# encoderBreakout1.net
KiCad netlist of a schematic drawn in Altium Designer
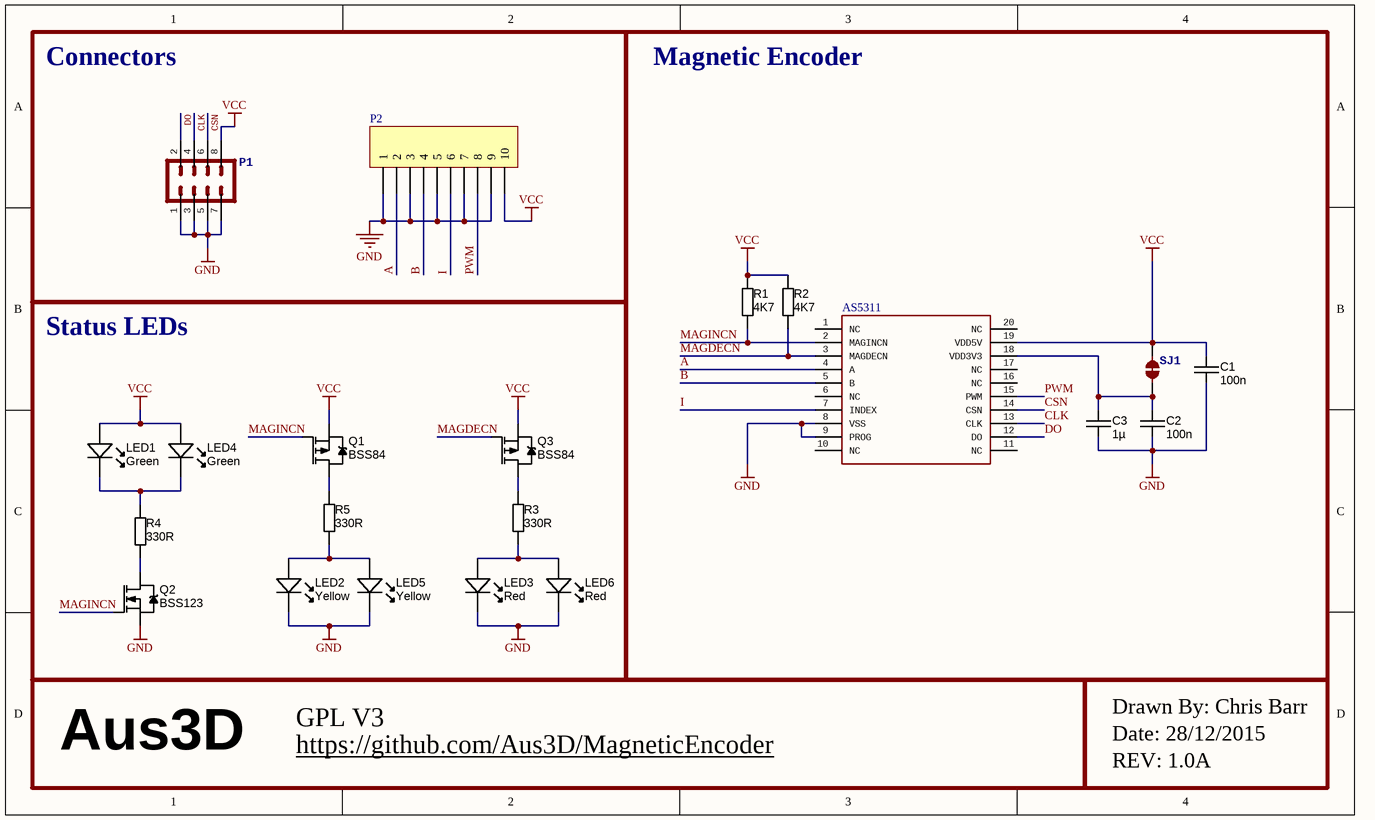
[diagram p0: encoderBreakout1.SchDoc]

(export (version "E")
  (design (tool "Eeschema 10.0.6"))
  (components
    (comp (ref "Aus3D")
      (value "Aus3D")
      (footprint "Aus3D-Logo")
      (libsource (lib "Schlib1") (part "Aus3D Logo"))
    )
    (comp (ref "C1")
      (value "100n")
      (footprint "CAPC1608X90N")
      (description "Capacitor SMD Cer 100nF 10% 50V X7R 0603")
      (fields (field (name "TOLERANCE") "±10%") (field (name "Comment") "approved sub OK"))
      (libsource (lib "PBL - Capacitors") (part "CAPC_100n_0603_X7R_50V_10%"))
    )
    (comp (ref "C2")
      (value "100n")
      (footprint "CAPC1608X90N")
      (description "Capacitor SMD Cer 100nF 10% 50V X7R 0603")
      (fields (field (name "TOLERANCE") "±10%") (field (name "Comment") "approved sub OK"))
      (libsource (lib "PBL - Capacitors") (part "CAPC_100n_0603_X7R_50V_10%"))
    )
    (comp (ref "C3")
      (value "1µ")
      (footprint "CAPC1608X90N")
      (description "Capacitor SMD Cer 1uF 10% 16V X7R 0603")
      (fields (field (name "TOLERANCE") "±10%") (field (name "Comment") "approved sub OK"))
      (libsource (lib "PBL - Capacitors") (part "CAPC_1u_0603_X7R_16V_10%"))
    )
    (comp (ref "LED1")
      (value "Green")
      (footprint "LED-0603-GREEN")
      (description "LED 0603 SMD Green 570nm 50mcd 20mA")
      (libsource (lib "PBL - Light Sources") (part "LED_SMD_Green_0603_570nm"))
    )
    (comp (ref "LED2")
      (value "Yellow")
      (footprint "LED-0603-YELLOW")
      (description "LED 0603 SMD Yellow 590nm 150mcd 20mA")
      (libsource (lib "PBL - Light Sources") (part "LED_SMD_Yellow_0603_150mcd"))
    )
    (comp (ref "LED3")
      (value "Red")
      (footprint "LED-0603-RED")
      (description "LED 0603 SMD Hyper Red 630nm 220mcd 20mA")
      (libsource (lib "PBL - Light Sources") (part "LED_SMD_Red_0603_220mcd"))
    )
    (comp (ref "LED4")
      (value "Green")
      (footprint "LED-0603-GREEN")
      (description "LED 0603 SMD Green 570nm 50mcd 20mA")
      (libsource (lib "PBL - Light Sources") (part "LED_SMD_Green_0603_570nm"))
    )
    (comp (ref "LED5")
      (value "Yellow")
      (footprint "LED-0603-YELLOW")
      (description "LED 0603 SMD Yellow 590nm 150mcd 20mA")
      (libsource (lib "PBL - Light Sources") (part "LED_SMD_Yellow_0603_150mcd"))
    )
    (comp (ref "LED6")
      (value "Red")
      (footprint "LED-0603-RED")
      (description "LED 0603 SMD Hyper Red 630nm 220mcd 20mA")
      (libsource (lib "PBL - Light Sources") (part "LED_SMD_Red_0603_220mcd"))
    )
    (comp (ref "P1")
      (value ".1\" header, two rows of four.")
      (footprint "2X4")
      (libsource (lib "SparkFun-Connectors") (part "M04X2"))
    )
    (comp (ref "P2")
      (value "Header 10")
      (footprint "HDR1X10")
      (description "Header, 10-Pin")
      (fields (field (name "PUBLISHER") "Altium Limited"))
      (libsource (lib "Miscellaneous Connectors") (part "Header 10"))
    )
    (comp (ref "Q1")
      (value "BSS84")
      (footprint "SOT23-3")
      (description "MOSFET SMD P-CH 50V 130mA SOT23-3")
      (libsource (lib "PBL - Transistors") (part "MOSFET_BSS84"))
    )
    (comp (ref "Q2")
      (value "BSS123")
      (footprint "SOT23-3")
      (description "MOSFET SMD N-CH 100V 170mA SOT23-3")
      (libsource (lib "PBL - Transistors") (part "MOSFET_BSS123"))
    )
    (comp (ref "Q3")
      (value "BSS84")
      (footprint "SOT23-3")
      (description "MOSFET SMD P-CH 50V 130mA SOT23-3")
      (libsource (lib "PBL - Transistors") (part "MOSFET_BSS84"))
    )
    (comp (ref "R1")
      (value "4K7")
      (footprint "RESC1608X55N")
      (description "Resistor SMD chip 4.7k Ohm 0.1W 5% 0603")
      (fields (field (name "TOLERANCE") "±5%") (field (name "Comment") "Thick Film"))
      (libsource (lib "PBL - Resistors") (part "RES_4K7_0603_5%"))
    )
    (comp (ref "R2")
      (value "4K7")
      (footprint "RESC1608X55N")
      (description "Resistor SMD chip 4.7k Ohm 0.1W 5% 0603")
      (fields (field (name "TOLERANCE") "±5%") (field (name "Comment") "Thick Film"))
      (libsource (lib "PBL - Resistors") (part "RES_4K7_0603_5%"))
    )
    (comp (ref "R3")
      (value "330R")
      (footprint "RESC1608X55N")
      (description "Resistor SMD chip 330 Ohm 0.1W 5% 0603")
      (fields (field (name "TOLERANCE") "±5%") (field (name "Comment") "Thick Film"))
      (libsource (lib "PBL - Resistors") (part "RES_330R_0603_5%"))
    )
    (comp (ref "R4")
      (value "330R")
      (footprint "RESC1608X55N")
      (description "Resistor SMD chip 330 Ohm 0.1W 5% 0603")
      (fields (field (name "TOLERANCE") "±5%") (field (name "Comment") "Thick Film"))
      (libsource (lib "PBL - Resistors") (part "RES_330R_0603_5%"))
    )
    (comp (ref "R5")
      (value "330R")
      (footprint "RESC1608X55N")
      (description "Resistor SMD chip 330 Ohm 0.1W 5% 0603")
      (fields (field (name "TOLERANCE") "±5%") (field (name "Comment") "Thick Film"))
      (libsource (lib "PBL - Resistors") (part "RES_330R_0603_5%"))
    )
    (comp (ref "SJ1")
      (value "JUMPER-PAD-2-NC_BY_TRACE")
      (footprint "PAD-JUMPER-2-NC_BY_TRACE_YES_SILK")
      (libsource (lib "SparkFun-Passives") (part "JUMPER-PAD-2-NC_BY_TRACE"))
    )
    (comp (ref "U1")
      (value "AS5311")
      (footprint "TSSOP-20")
      (description "AMS's AS5311 linear hall-effect encoder.")
      (libsource (lib "ams") (part "AS5311"))
    )
  )
  (nets
    (net (code "1") (name "/A") (class "Default")
      (node (ref "P2") (pin "2") (pinfunction "2_2") (pintype "passive"))
      (node (ref "U1") (pin "4") (pinfunction "A_4") (pintype "passive"))
    )
    (net (code "2") (name "/B") (class "Default")
      (node (ref "P2") (pin "4") (pinfunction "4_4") (pintype "passive"))
      (node (ref "U1") (pin "5") (pinfunction "B_5") (pintype "passive"))
    )
    (net (code "3") (name "/CLK") (class "Default")
      (node (ref "P1") (pin "4") (pinfunction "4_4") (pintype "passive"))
      (node (ref "U1") (pin "13") (pinfunction "CLK_13") (pintype "passive"))
    )
    (net (code "4") (name "/CSN") (class "Default")
      (node (ref "P1") (pin "6") (pinfunction "6_6") (pintype "passive"))
      (node (ref "U1") (pin "14") (pinfunction "CSN_14") (pintype "passive"))
    )
    (net (code "5") (name "/DO") (class "Default")
      (node (ref "P1") (pin "2") (pinfunction "2_2") (pintype "passive"))
      (node (ref "U1") (pin "12") (pinfunction "DO_12") (pintype "passive"))
    )
    (net (code "6") (name "/I") (class "Default")
      (node (ref "P2") (pin "6") (pinfunction "6_6") (pintype "passive"))
      (node (ref "U1") (pin "7") (pinfunction "INDEX_7") (pintype "passive"))
    )
    (net (code "7") (name "/MAGDECN") (class "Default")
      (node (ref "Q3") (pin "1") (pinfunction "G_1") (pintype "passive"))
      (node (ref "R2") (pin "2") (pinfunction "2_2") (pintype "passive"))
      (node (ref "U1") (pin "3") (pinfunction "MAGDECN_3") (pintype "passive"))
    )
    (net (code "8") (name "/MAGINCN") (class "Default")
      (node (ref "Q1") (pin "1") (pinfunction "G_1") (pintype "passive"))
      (node (ref "Q2") (pin "1") (pinfunction "G_1") (pintype "passive"))
      (node (ref "R1") (pin "2") (pinfunction "2_2") (pintype "passive"))
      (node (ref "U1") (pin "2") (pinfunction "MAGINCN_2") (pintype "passive"))
    )
    (net (code "9") (name "/PWM") (class "Default")
      (node (ref "P2") (pin "8") (pinfunction "8_8") (pintype "passive"))
      (node (ref "U1") (pin "15") (pinfunction "PWM_15") (pintype "passive"))
    )
    (net (code "10") (name "GND") (class "Default")
      (node (ref "C1") (pin "2") (pintype "passive"))
      (node (ref "C2") (pin "2") (pintype "passive"))
      (node (ref "C3") (pin "2") (pintype "passive"))
      (node (ref "LED2") (pin "K") (pinfunction "K_K") (pintype "passive"))
      (node (ref "LED3") (pin "K") (pinfunction "K_K") (pintype "passive"))
      (node (ref "LED5") (pin "K") (pinfunction "K_K") (pintype "passive"))
      (node (ref "LED6") (pin "K") (pinfunction "K_K") (pintype "passive"))
      (node (ref "P1") (pin "1") (pinfunction "1_1") (pintype "passive"))
      (node (ref "P1") (pin "3") (pinfunction "3_3") (pintype "passive"))
      (node (ref "P1") (pin "5") (pinfunction "5_5") (pintype "passive"))
      (node (ref "P1") (pin "7") (pinfunction "7_7") (pintype "passive"))
      (node (ref "P2") (pin "1") (pinfunction "1_1") (pintype "passive"))
      (node (ref "P2") (pin "3") (pinfunction "3_3") (pintype "passive"))
      (node (ref "P2") (pin "5") (pinfunction "5_5") (pintype "passive"))
      (node (ref "P2") (pin "7") (pinfunction "7_7") (pintype "passive"))
      (node (ref "P2") (pin "9") (pinfunction "9_9") (pintype "passive"))
      (node (ref "Q2") (pin "2") (pinfunction "S_2") (pintype "passive"))
      (node (ref "U1") (pin "8") (pinfunction "VSS_8") (pintype "power_in"))
      (node (ref "U1") (pin "9") (pinfunction "PROG_9") (pintype "passive"))
    )
    (net (code "11") (name "Net-(LED1-PadK)") (class "Default")
      (node (ref "LED1") (pin "K") (pinfunction "K_K") (pintype "passive"))
      (node (ref "LED4") (pin "K") (pinfunction "K_K") (pintype "passive"))
      (node (ref "R4") (pin "1") (pinfunction "1_1") (pintype "passive"))
    )
    (net (code "12") (name "Net-(LED2-PadA)") (class "Default")
      (node (ref "LED2") (pin "A") (pinfunction "A_A") (pintype "passive"))
      (node (ref "LED5") (pin "A") (pinfunction "A_A") (pintype "passive"))
      (node (ref "R5") (pin "2") (pinfunction "2_2") (pintype "passive"))
    )
    (net (code "13") (name "Net-(LED3-PadA)") (class "Default")
      (node (ref "LED3") (pin "A") (pinfunction "A_A") (pintype "passive"))
      (node (ref "LED6") (pin "A") (pinfunction "A_A") (pintype "passive"))
      (node (ref "R3") (pin "2") (pinfunction "2_2") (pintype "passive"))
    )
    (net (code "14") (name "Net-(Q1-D)") (class "Default")
      (node (ref "Q1") (pin "3") (pinfunction "D_3") (pintype "passive"))
      (node (ref "R5") (pin "1") (pinfunction "1_1") (pintype "passive"))
    )
    (net (code "15") (name "Net-(Q2-D)") (class "Default")
      (node (ref "Q2") (pin "3") (pinfunction "D_3") (pintype "passive"))
      (node (ref "R4") (pin "2") (pinfunction "2_2") (pintype "passive"))
    )
    (net (code "16") (name "Net-(Q3-D)") (class "Default")
      (node (ref "Q3") (pin "3") (pinfunction "D_3") (pintype "passive"))
      (node (ref "R3") (pin "1") (pinfunction "1_1") (pintype "passive"))
    )
    (net (code "17") (name "Net-(U1-VDD3V3)") (class "Default")
      (node (ref "C2") (pin "1") (pintype "passive"))
      (node (ref "C3") (pin "1") (pintype "passive"))
      (node (ref "SJ1") (pin "1") (pinfunction "1_1") (pintype "passive"))
      (node (ref "U1") (pin "18") (pinfunction "VDD3V3_18") (pintype "open_emitter"))
    )
    (net (code "18") (name "VCC") (class "Default")
      (node (ref "C1") (pin "1") (pintype "passive"))
      (node (ref "LED1") (pin "A") (pinfunction "A_A") (pintype "passive"))
      (node (ref "LED4") (pin "A") (pinfunction "A_A") (pintype "passive"))
      (node (ref "P1") (pin "8") (pinfunction "8_8") (pintype "passive"))
      (node (ref "P2") (pin "10") (pinfunction "10_10") (pintype "passive"))
      (node (ref "Q1") (pin "2") (pinfunction "S_2") (pintype "passive"))
      (node (ref "Q3") (pin "2") (pinfunction "S_2") (pintype "passive"))
      (node (ref "R1") (pin "1") (pinfunction "1_1") (pintype "passive"))
      (node (ref "R2") (pin "1") (pinfunction "1_1") (pintype "passive"))
      (node (ref "SJ1") (pin "2") (pinfunction "2_2") (pintype "passive"))
      (node (ref "U1") (pin "19") (pinfunction "VDD5V_19") (pintype "open_emitter"))
    )
    (net (code "19") (name "unconnected-(U1-NC-Pad1)") (class "Default")
      (node (ref "U1") (pin "1") (pinfunction "NC_1") (pintype "passive"))
    )
    (net (code "20") (name "unconnected-(U1-NC-Pad6)") (class "Default")
      (node (ref "U1") (pin "6") (pinfunction "NC_6") (pintype "passive"))
    )
    (net (code "21") (name "unconnected-(U1-NC-Pad10)") (class "Default")
      (node (ref "U1") (pin "10") (pinfunction "NC_10") (pintype "passive"))
    )
    (net (code "22") (name "unconnected-(U1-NC-Pad11)") (class "Default")
      (node (ref "U1") (pin "11") (pinfunction "NC_11") (pintype "passive"))
    )
    (net (code "23") (name "unconnected-(U1-NC-Pad16)") (class "Default")
      (node (ref "U1") (pin "16") (pinfunction "NC_16") (pintype "passive"))
    )
    (net (code "24") (name "unconnected-(U1-NC-Pad17)") (class "Default")
      (node (ref "U1") (pin "17") (pinfunction "NC_17") (pintype "passive"))
    )
    (net (code "25") (name "unconnected-(U1-NC-Pad20)") (class "Default")
      (node (ref "U1") (pin "20") (pinfunction "NC_20") (pintype "passive"))
    )
  )
)
